# LMT87.net
KiCad netlist of a schematic drawn in Altium Designer
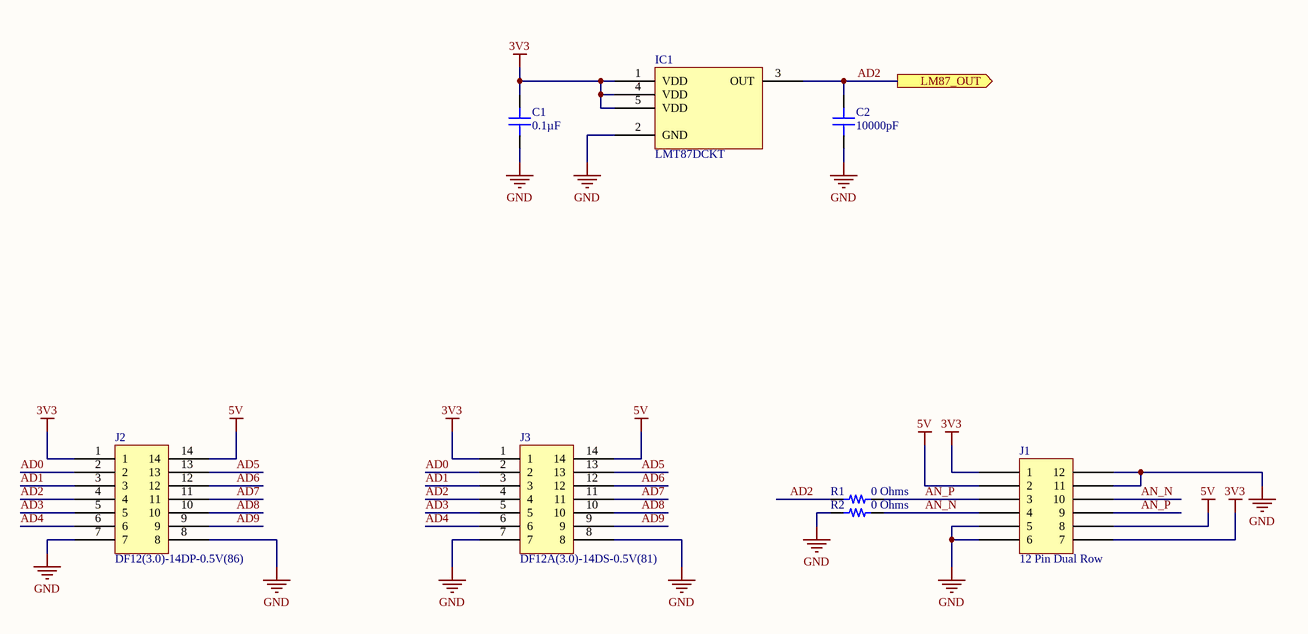
[diagram p0: LMT87.SchDoc]

(export (version "E")
  (design (tool "Eeschema 10.0.6"))
  (components
    (comp (ref "C1")
      (value "0.1µF")
      (footprint "CAP 0603_1608")
      (description "CAP CER 0.1UF 16V Y5V 0603")
      (fields (field (name "PART NUMBER") "CC0603ZRY5V7BB104") (field (name "MANUFACTURER") "Yageo"))
      (libsource (lib "altiumlibrary.com") (part "Capacitor"))
    )
    (comp (ref "C2")
      (value "10000pF")
      (footprint "CAP 0603_1608")
      (description "CAP CER 10000PF 50V X7R 0603")
      (fields (field (name "PART NUMBER") "AC0603KPX7R9BB103") (field (name "MANUFACTURER") "Yageo"))
      (libsource (lib "altiumlibrary.com") (part "Capacitor"))
    )
    (comp (ref "IC1")
      (value "LMT87DCKT")
      (footprint "TI SC-70-5 DCK")
      (description "SENSOR ANALOG -50C-150C SC70-5")
      (fields (field (name "MANUFACTURER") "Texas Instruments"))
      (libsource (lib "altiumlibrary.com") (part "TI LMT87"))
    )
    (comp (ref "J1")
      (value "12 Pin Dual Row")
      (footprint "TE 5650118-3 Card Edge")
      (libsource (lib "CelestialUseful") (part "12 Pin Dual Row"))
    )
    (comp (ref "J2")
      (value "DF12(3.0)-14DP-0.5V(86)")
      (footprint "HIROSE DF12 3.0-14DP-0.5V 86")
      (description "CONN HDR 14POS SMD GOLD")
      (fields (field (name "MANUFACTURER") "Hirose Electric Co Ltd"))
      (libsource (lib "altiumlibrary.com") (part "14 Pin Dual Row"))
    )
    (comp (ref "J3")
      (value "DF12A(3.0)-14DS-0.5V(81)")
      (footprint "HIROSE DF12A 3.0-14DS-0.5V 81")
      (description "CONN RCPT 14POS SMD GOLD")
      (fields (field (name "MANUFACTURER") "Hirose Electric Co Ltd"))
      (libsource (lib "altiumlibrary.com") (part "14 Pin Dual Row"))
    )
    (comp (ref "R1")
      (value "0 Ohms")
      (footprint "RES 0603_1608")
      (description "RES SMD 0 OHM JUMPER 1/10W 0603")
      (fields
        (field (name "PART NUMBER") "ERJ-3GEY0R00V")
        (field (name "MANUFACTURER") "Panasonic Electronic Components")
      )
      (libsource (lib "altiumlibrary.com") (part "Resistor"))
    )
    (comp (ref "R2")
      (value "0 Ohms")
      (footprint "RES 0603_1608")
      (description "RES SMD 0 OHM JUMPER 1/10W 0603")
      (fields
        (field (name "PART NUMBER") "ERJ-3GEY0R00V")
        (field (name "MANUFACTURER") "Panasonic Electronic Components")
      )
      (libsource (lib "altiumlibrary.com") (part "Resistor"))
    )
  )
  (nets
    (net (code "1") (name "/AD0") (class "Default")
      (node (ref "J2") (pin "2") (pinfunction "2_2") (pintype "passive"))
      (node (ref "J3") (pin "2") (pinfunction "2_2") (pintype "passive"))
    )
    (net (code "2") (name "/AD1") (class "Default")
      (node (ref "J2") (pin "3") (pinfunction "3_3") (pintype "passive"))
      (node (ref "J3") (pin "3") (pinfunction "3_3") (pintype "passive"))
    )
    (net (code "3") (name "/AD2") (class "Default")
      (node (ref "C2") (pin "2") (pinfunction "2_2") (pintype "passive"))
      (node (ref "IC1") (pin "3") (pinfunction "OUT_3") (pintype "passive"))
      (node (ref "J2") (pin "4") (pinfunction "4_4") (pintype "passive"))
      (node (ref "J3") (pin "4") (pinfunction "4_4") (pintype "passive"))
      (node (ref "R1") (pin "1") (pinfunction "1_1") (pintype "passive"))
    )
    (net (code "4") (name "/AD3") (class "Default")
      (node (ref "J2") (pin "5") (pinfunction "5_5") (pintype "passive"))
      (node (ref "J3") (pin "5") (pinfunction "5_5") (pintype "passive"))
    )
    (net (code "5") (name "/AD4") (class "Default")
      (node (ref "J2") (pin "6") (pinfunction "6_6") (pintype "passive"))
      (node (ref "J3") (pin "6") (pinfunction "6_6") (pintype "passive"))
    )
    (net (code "6") (name "/AD5") (class "Default")
      (node (ref "J2") (pin "13") (pinfunction "13_13") (pintype "passive"))
      (node (ref "J3") (pin "13") (pinfunction "13_13") (pintype "passive"))
    )
    (net (code "7") (name "/AD6") (class "Default")
      (node (ref "J2") (pin "12") (pinfunction "12_12") (pintype "passive"))
      (node (ref "J3") (pin "12") (pinfunction "12_12") (pintype "passive"))
    )
    (net (code "8") (name "/AD7") (class "Default")
      (node (ref "J2") (pin "11") (pinfunction "11_11") (pintype "passive"))
      (node (ref "J3") (pin "11") (pinfunction "11_11") (pintype "passive"))
    )
    (net (code "9") (name "/AD8") (class "Default")
      (node (ref "J2") (pin "10") (pinfunction "10_10") (pintype "passive"))
      (node (ref "J3") (pin "10") (pinfunction "10_10") (pintype "passive"))
    )
    (net (code "10") (name "/AD9") (class "Default")
      (node (ref "J2") (pin "9") (pinfunction "9_9") (pintype "passive"))
      (node (ref "J3") (pin "9") (pinfunction "9_9") (pintype "passive"))
    )
    (net (code "11") (name "/AN_N") (class "Default")
      (node (ref "J1") (pin "10") (pinfunction "10_10") (pintype "passive"))
      (node (ref "J1") (pin "4") (pinfunction "4_4") (pintype "passive"))
      (node (ref "R2") (pin "2") (pinfunction "2_2") (pintype "passive"))
    )
    (net (code "12") (name "/AN_P") (class "Default")
      (node (ref "J1") (pin "3") (pinfunction "3_3") (pintype "passive"))
      (node (ref "J1") (pin "9") (pinfunction "9_9") (pintype "passive"))
      (node (ref "R1") (pin "2") (pinfunction "2_2") (pintype "passive"))
    )
    (net (code "13") (name "3V3") (class "Default")
      (node (ref "C1") (pin "1") (pinfunction "1_1") (pintype "passive"))
      (node (ref "IC1") (pin "1") (pinfunction "VDD_1") (pintype "passive"))
      (node (ref "IC1") (pin "4") (pinfunction "VDD_4") (pintype "passive"))
      (node (ref "IC1") (pin "5") (pinfunction "VDD_5") (pintype "passive"))
      (node (ref "J1") (pin "1") (pinfunction "1_1") (pintype "passive"))
      (node (ref "J1") (pin "7") (pinfunction "7_7") (pintype "passive"))
      (node (ref "J2") (pin "1") (pinfunction "1_1") (pintype "passive"))
      (node (ref "J3") (pin "1") (pinfunction "1_1") (pintype "passive"))
    )
    (net (code "14") (name "5V") (class "Default")
      (node (ref "J1") (pin "2") (pinfunction "2_2") (pintype "passive"))
      (node (ref "J1") (pin "8") (pinfunction "8_8") (pintype "passive"))
      (node (ref "J2") (pin "14") (pinfunction "14_14") (pintype "passive"))
      (node (ref "J3") (pin "14") (pinfunction "14_14") (pintype "passive"))
    )
    (net (code "15") (name "GND") (class "Default")
      (node (ref "C1") (pin "2") (pinfunction "2_2") (pintype "passive"))
      (node (ref "C2") (pin "1") (pinfunction "1_1") (pintype "passive"))
      (node (ref "IC1") (pin "2") (pinfunction "GND_2") (pintype "passive"))
      (node (ref "J1") (pin "11") (pinfunction "11_11") (pintype "passive"))
      (node (ref "J1") (pin "12") (pinfunction "12_12") (pintype "passive"))
      (node (ref "J1") (pin "5") (pinfunction "5_5") (pintype "passive"))
      (node (ref "J1") (pin "6") (pinfunction "6_6") (pintype "passive"))
      (node (ref "J2") (pin "7") (pinfunction "7_7") (pintype "passive"))
      (node (ref "J2") (pin "8") (pinfunction "8_8") (pintype "passive"))
      (node (ref "J3") (pin "7") (pinfunction "7_7") (pintype "passive"))
      (node (ref "J3") (pin "8") (pinfunction "8_8") (pintype "passive"))
      (node (ref "R2") (pin "1") (pinfunction "1_1") (pintype "passive"))
    )
  )
)
